# Main.net
KiCad netlist of a schematic drawn in Altium Designer
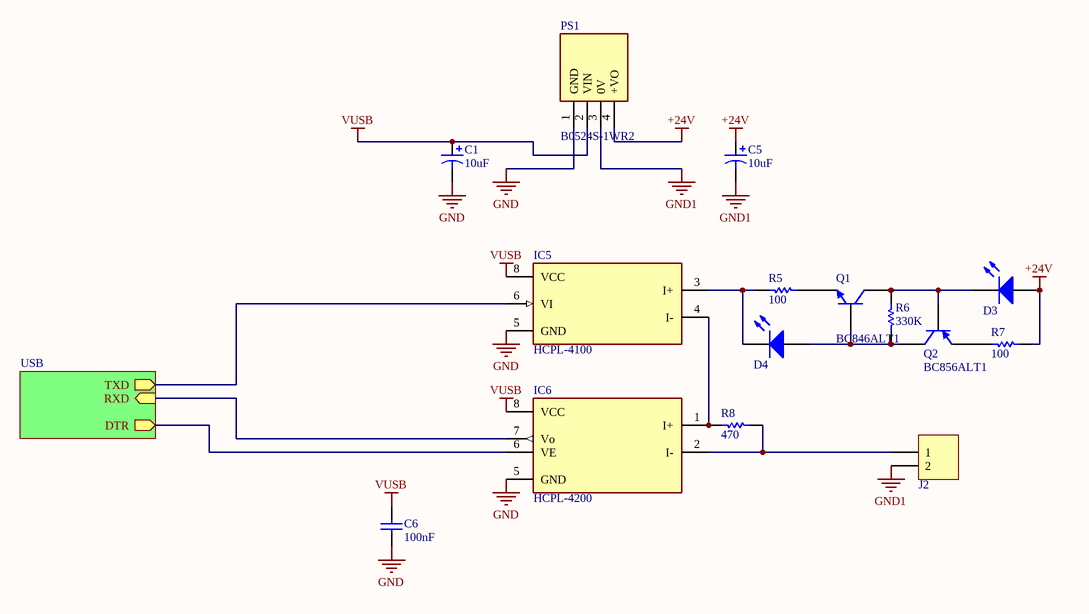
[diagram p0: Main.SchDoc]

(export (version "E")
  (design (tool "Eeschema 10.0.6"))
  (components
    (comp (ref "C1")
      (value "10uF")
      (footprint "CAP-TAN-A")
      (description "Polar Capacitor")
      (fields (field (name "VOLTAGE") "10V"))
      (libsource (lib "ParsaLibrary") (part "CAP-POL"))
    )
    (comp (ref "C5")
      (value "10uF")
      (footprint "CAP-TAN-A")
      (description "Polar Capacitor")
      (fields (field (name "VOLTAGE") "10V"))
      (libsource (lib "ParsaLibrary") (part "CAP-POL"))
    )
    (comp (ref "C6")
      (value "100nF")
      (footprint "C603")
      (description "Capacitor")
      (fields (field (name "DESIGNER") "Parsa Malekpour"))
      (libsource (lib "ParsaLibrary") (part "Cap"))
    )
    (comp (ref "D3") (value "LED") (footprint "LED-0603") (libsource (lib "ParsaLibrary") (part "LED")))
    (comp (ref "D4") (value "LED") (footprint "LED-0603") (libsource (lib "ParsaLibrary") (part "LED")))
    (comp (ref "IC5")
      (value "HCPL-4100")
      (footprint "ParsaLibrary:SOP-8")
      (description "<b>Isolation Amplifer</b><p> Source: http://www.avagotech.com/docs/AV02-0410EN")
      (fields (field (name "MF") "{'manufacturer': u'Broadcom Limited'}"))
      (libsource (lib "ParsaLibrary") (part "HCPL-4100"))
    )
    (comp (ref "IC6")
      (value "HCPL-4200")
      (footprint "PARSALIBRARY:SOP-8")
      (description "Optically Coupled 20 mA Current Loop Receiver")
      (fields (field (name "MF") "{'manufacturer': u'Broadcom Limited'}") (field (name "MP") "HCPL-4100"))
      (libsource (lib "ParsaLibrary") (part "HCPL-4200"))
    )
    (comp (ref "J2") (value "CONN-2") (footprint "phonix-2") (libsource (lib "ParsaLibrary") (part "CONN-2")))
    (comp (ref "PS1")
      (value "B0524S-1WR2")
      (footprint "SamacSys:B0524S1WR2")
      (description "Power Supply")
      (libsource (lib "*") (part "B0524S-1WR2"))
    )
    (comp (ref "Q1")
      (value "BC846ALT1")
      (footprint "SOT-23")
      (description "General Purpose Transistor NPN Silicon")
      (fields (field (name "PUBLISHER") "Altium Limited"))
      (libsource (lib "Motorola Discrete BJT") (part "BC846ALT1"))
    )
    (comp (ref "Q2")
      (value "BC856ALT1")
      (footprint "SOT-23")
      (description "General Purpose Transistor PNP Silicon")
      (fields (field (name "PUBLISHER") "Altium Limited"))
      (libsource (lib "Motorola Discrete BJT") (part "BC856ALT1"))
    )
    (comp (ref "R5")
      (value "100")
      (footprint "r0603")
      (description "Resistor")
      (fields (field (name "DESIGNER") "Parsa Malekpour"))
      (libsource (lib "ParsaLibrary") (part "Resistor"))
    )
    (comp (ref "R6")
      (value "330K")
      (footprint "r0603")
      (description "Resistor")
      (fields (field (name "DESIGNER") "Parsa Malekpour"))
      (libsource (lib "ParsaLibrary") (part "Resistor"))
    )
    (comp (ref "R7")
      (value "100")
      (footprint "r0603")
      (description "Resistor")
      (fields (field (name "DESIGNER") "Parsa Malekpour"))
      (libsource (lib "ParsaLibrary") (part "Resistor"))
    )
    (comp (ref "R8")
      (value "470")
      (footprint "R805")
      (description "Resistor")
      (fields (field (name "DESIGNER") "Parsa Malekpour"))
      (libsource (lib "ParsaLibrary") (part "Resistor"))
    )
  )
  (nets
    (net (code "1") (name "+24V") (class "Default")
      (node (ref "C5") (pin "1") (pinfunction "1_1") (pintype "passive"))
      (node (ref "D3") (pin "1") (pinfunction "A_1") (pintype "passive"))
      (node (ref "PS1") (pin "4") (pinfunction "+VO_4") (pintype "passive"))
      (node (ref "R7") (pin "2") (pinfunction "2_2") (pintype "passive"))
    )
    (net (code "2") (name "/DTR") (class "Default")
      (node (ref "IC6") (pin "6") (pinfunction "VE_6") (pintype "power_in"))
    )
    (net (code "3") (name "/RXD") (class "Default")
      (node (ref "IC6") (pin "7") (pinfunction "Vo_7") (pintype "output"))
    )
    (net (code "4") (name "/TXD") (class "Default")
      (node (ref "IC5") (pin "6") (pinfunction "VI_6") (pintype "input"))
    )
    (net (code "5") (name "GND") (class "Default")
      (node (ref "C1") (pin "2") (pinfunction "2_2") (pintype "passive"))
      (node (ref "C6") (pin "1") (pinfunction "1_1") (pintype "passive"))
      (node (ref "IC5") (pin "5") (pinfunction "GND_5") (pintype "power_in"))
      (node (ref "IC6") (pin "5") (pinfunction "GND_5") (pintype "power_in"))
      (node (ref "PS1") (pin "1") (pinfunction "GND_1") (pintype "passive"))
    )
    (net (code "6") (name "GND1") (class "Default")
      (node (ref "C5") (pin "2") (pinfunction "2_2") (pintype "passive"))
      (node (ref "J2") (pin "2") (pinfunction "2_2") (pintype "passive"))
      (node (ref "PS1") (pin "3") (pinfunction "0V_3") (pintype "passive"))
    )
    (net (code "7") (name "Net-(D3-K)") (class "Default")
      (node (ref "D3") (pin "2") (pinfunction "K_2") (pintype "passive"))
      (node (ref "Q1") (pin "3") (pinfunction "C_3") (pintype "passive"))
      (node (ref "Q2") (pin "1") (pinfunction "B_1") (pintype "passive"))
      (node (ref "R6") (pin "1") (pinfunction "1_1") (pintype "passive"))
    )
    (net (code "8") (name "Net-(D4-A)") (class "Default")
      (node (ref "D4") (pin "1") (pinfunction "A_1") (pintype "passive"))
      (node (ref "Q1") (pin "1") (pinfunction "B_1") (pintype "passive"))
      (node (ref "Q2") (pin "3") (pinfunction "C_3") (pintype "passive"))
      (node (ref "R6") (pin "2") (pinfunction "2_2") (pintype "passive"))
    )
    (net (code "9") (name "Net-(D4-K)") (class "Default")
      (node (ref "D4") (pin "2") (pinfunction "K_2") (pintype "passive"))
      (node (ref "IC5") (pin "3") (pinfunction "I+_3") (pintype "power_in"))
      (node (ref "R5") (pin "1") (pinfunction "1_1") (pintype "passive"))
    )
    (net (code "10") (name "Net-(IC5-I-)") (class "Default")
      (node (ref "IC5") (pin "4") (pinfunction "I-_4") (pintype "power_in"))
      (node (ref "IC6") (pin "1") (pinfunction "I+_1") (pintype "power_in"))
      (node (ref "R8") (pin "2") (pinfunction "2_2") (pintype "passive"))
    )
    (net (code "11") (name "Net-(IC6-I-)") (class "Default")
      (node (ref "IC6") (pin "2") (pinfunction "I-_2") (pintype "power_in"))
      (node (ref "J2") (pin "1") (pinfunction "1_1") (pintype "passive"))
      (node (ref "R8") (pin "1") (pinfunction "1_1") (pintype "passive"))
    )
    (net (code "12") (name "Net-(Q1-E)") (class "Default")
      (node (ref "Q1") (pin "2") (pinfunction "E_2") (pintype "passive"))
      (node (ref "R5") (pin "2") (pinfunction "2_2") (pintype "passive"))
    )
    (net (code "13") (name "Net-(Q2-E)") (class "Default")
      (node (ref "Q2") (pin "2") (pinfunction "E_2") (pintype "passive"))
      (node (ref "R7") (pin "1") (pinfunction "1_1") (pintype "passive"))
    )
    (net (code "14") (name "VUSB") (class "Default")
      (node (ref "C1") (pin "1") (pinfunction "1_1") (pintype "passive"))
      (node (ref "C6") (pin "2") (pinfunction "2_2") (pintype "passive"))
      (node (ref "IC5") (pin "8") (pinfunction "VCC_8") (pintype "power_in"))
      (node (ref "IC6") (pin "8") (pinfunction "VCC_8") (pintype "power_in"))
      (node (ref "PS1") (pin "2") (pinfunction "VIN_2") (pintype "passive"))
    )
  )
)
